# Arduino-UNO-Sheild.net
KiCad netlist of a schematic drawn in EAGLE
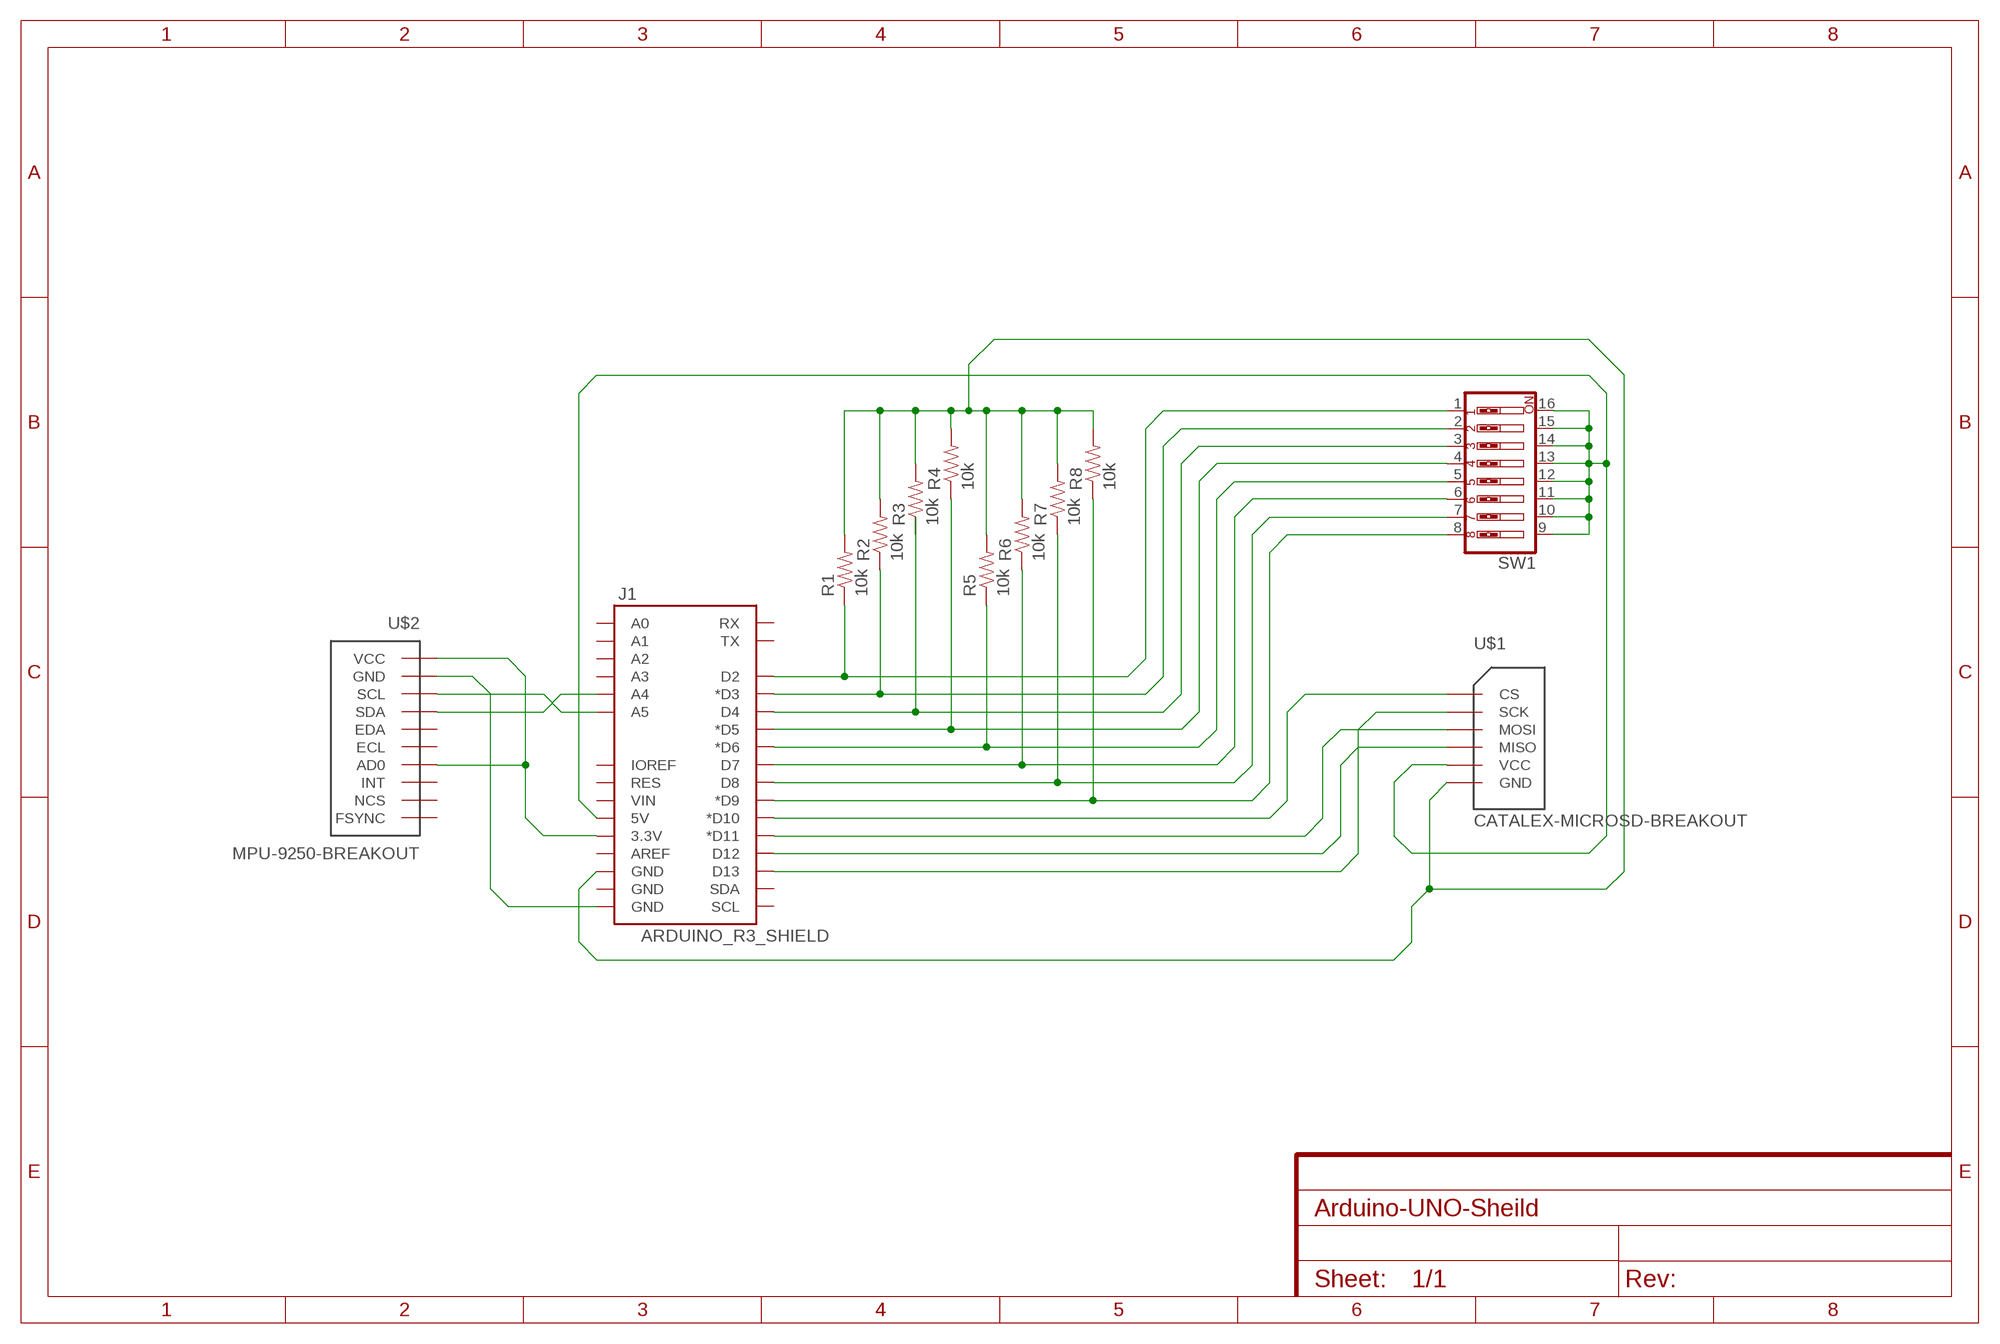
[diagram p0: schematic, sheet 1]

(export (version "E")
  (design (tool "Eeschema 10.0.6"))
  (components
    (comp (ref "J1")
      (value "ARDUINO_R3_SHIELD")
      (footprint "eagle-import:UNO_R3_SHIELD")
      (libsource (lib "eagle-import") (part "ARDUINO_R3_SHIELD"))
    )
    (comp (ref "R1")
      (value "10k")
      (footprint "eagle-import:AXIAL-0.3-KIT")
      (libsource (lib "eagle-import") (part "RESISTORKIT"))
    )
    (comp (ref "R2")
      (value "10k")
      (footprint "eagle-import:AXIAL-0.3-KIT")
      (libsource (lib "eagle-import") (part "RESISTORKIT"))
    )
    (comp (ref "R3")
      (value "10k")
      (footprint "eagle-import:AXIAL-0.3-KIT")
      (libsource (lib "eagle-import") (part "RESISTORKIT"))
    )
    (comp (ref "R4")
      (value "10k")
      (footprint "eagle-import:AXIAL-0.3-KIT")
      (libsource (lib "eagle-import") (part "RESISTORKIT"))
    )
    (comp (ref "R5")
      (value "10k")
      (footprint "eagle-import:AXIAL-0.3-KIT")
      (libsource (lib "eagle-import") (part "RESISTORKIT"))
    )
    (comp (ref "R6")
      (value "10k")
      (footprint "eagle-import:AXIAL-0.3-KIT")
      (libsource (lib "eagle-import") (part "RESISTORKIT"))
    )
    (comp (ref "R7")
      (value "10k")
      (footprint "eagle-import:AXIAL-0.3-KIT")
      (libsource (lib "eagle-import") (part "RESISTORKIT"))
    )
    (comp (ref "R8")
      (value "10k")
      (footprint "eagle-import:AXIAL-0.3-KIT")
      (libsource (lib "eagle-import") (part "RESISTORKIT"))
    )
    (comp (ref "SW1")
      (value "SW_DIP-8")
      (footprint "eagle-import:DIPSWITCH-08")
      (libsource (lib "eagle-import") (part "SW_DIP-8"))
    )
    (comp (ref "U$1")
      (value "CATALEX-MICROSD-BREAKOUT")
      (footprint "eagle-import:CATALEX-MICROSD-BREAKOUT")
      (libsource (lib "eagle-import") (part "CATALEX-MICROSD-BREAKOUT"))
    )
    (comp (ref "U$2")
      (value "MPU-9250-BREAKOUT")
      (footprint "eagle-import:MPU-9250-BREAKOUT")
      (libsource (lib "eagle-import") (part "MPU-9250-BREAKOUT"))
    )
  )
  (nets
    (net (code "1") (name "Net-(J1-*D3)") (class "Default")
      (node (ref "J1") (pin "D3") (pinfunction "*D3_D3") (pintype "bidirectional"))
      (node (ref "R2") (pin "P$1") (pinfunction "1_P$1") (pintype "passive"))
      (node (ref "SW1") (pin "2") (pinfunction "2_2") (pintype "passive"))
    )
    (net (code "2") (name "Net-(J1-*D5)") (class "Default")
      (node (ref "J1") (pin "D5") (pinfunction "*D5_D5") (pintype "bidirectional"))
      (node (ref "R4") (pin "P$1") (pinfunction "1_P$1") (pintype "passive"))
      (node (ref "SW1") (pin "4") (pinfunction "4_4") (pintype "passive"))
    )
    (net (code "3") (name "Net-(J1-*D6)") (class "Default")
      (node (ref "J1") (pin "D6") (pinfunction "*D6_D6") (pintype "bidirectional"))
      (node (ref "R5") (pin "P$1") (pinfunction "1_P$1") (pintype "passive"))
      (node (ref "SW1") (pin "5") (pinfunction "5_5") (pintype "passive"))
    )
    (net (code "4") (name "Net-(J1-*D9)") (class "Default")
      (node (ref "J1") (pin "D9") (pinfunction "*D9_D9") (pintype "bidirectional"))
      (node (ref "R8") (pin "P$1") (pinfunction "1_P$1") (pintype "passive"))
      (node (ref "SW1") (pin "8") (pinfunction "8_8") (pintype "passive"))
    )
    (net (code "5") (name "Net-(J1-*D10)") (class "Default")
      (node (ref "J1") (pin "D10") (pinfunction "*D10_D10") (pintype "bidirectional"))
      (node (ref "U$1") (pin "CS") (pinfunction "CS_CS") (pintype "bidirectional"))
    )
    (net (code "6") (name "Net-(J1-*D11)") (class "Default")
      (node (ref "J1") (pin "D11") (pinfunction "*D11_D11") (pintype "bidirectional"))
      (node (ref "U$1") (pin "MOSI") (pinfunction "MOSI_MOSI") (pintype "bidirectional"))
    )
    (net (code "7") (name "Net-(J1-GND-PadGND@0)") (class "Default")
      (node (ref "J1") (pin "GND@0") (pinfunction "GND_GND@0") (pintype "bidirectional"))
      (node (ref "U$2") (pin "GND") (pinfunction "GND_GND") (pintype "bidirectional"))
    )
    (net (code "8") (name "Net-(J1-Pad3.3V)") (class "Default")
      (node (ref "J1") (pin "3.3V") (pinfunction "3.3V_3.3V") (pintype "bidirectional"))
      (node (ref "U$2") (pin "AD0") (pinfunction "AD0_AD0") (pintype "bidirectional"))
      (node (ref "U$2") (pin "VCC") (pinfunction "VCC_VCC") (pintype "bidirectional"))
    )
    (net (code "9") (name "Net-(J1-Pad5V)") (class "Default")
      (node (ref "J1") (pin "5V") (pinfunction "5V_5V") (pintype "bidirectional"))
      (node (ref "SW1") (pin "10") (pinfunction "10_10") (pintype "passive"))
      (node (ref "SW1") (pin "11") (pinfunction "11_11") (pintype "passive"))
      (node (ref "SW1") (pin "12") (pinfunction "12_12") (pintype "passive"))
      (node (ref "SW1") (pin "13") (pinfunction "13_13") (pintype "passive"))
      (node (ref "SW1") (pin "14") (pinfunction "14_14") (pintype "passive"))
      (node (ref "SW1") (pin "15") (pinfunction "15_15") (pintype "passive"))
      (node (ref "SW1") (pin "16") (pinfunction "16_16") (pintype "passive"))
      (node (ref "SW1") (pin "9") (pinfunction "9_9") (pintype "passive"))
      (node (ref "U$1") (pin "VCC") (pinfunction "VCC_VCC") (pintype "bidirectional"))
    )
    (net (code "10") (name "Net-(J1-PadA4)") (class "Default")
      (node (ref "J1") (pin "A4") (pinfunction "A4_A4") (pintype "bidirectional"))
      (node (ref "U$2") (pin "SDA") (pinfunction "SDA_SDA") (pintype "bidirectional"))
    )
    (net (code "11") (name "Net-(J1-PadA5)") (class "Default")
      (node (ref "J1") (pin "A5") (pinfunction "A5_A5") (pintype "bidirectional"))
      (node (ref "U$2") (pin "SCL") (pinfunction "SCL_SCL") (pintype "bidirectional"))
    )
    (net (code "12") (name "Net-(J1-PadD4)") (class "Default")
      (node (ref "J1") (pin "D4") (pinfunction "D4_D4") (pintype "bidirectional"))
      (node (ref "SW1") (pin "3") (pinfunction "3_3") (pintype "passive"))
    )
    (net (code "13") (name "Net-(J1-PadD12)") (class "Default")
      (node (ref "J1") (pin "D12") (pinfunction "D12_D12") (pintype "bidirectional"))
      (node (ref "U$1") (pin "MISO") (pinfunction "MISO_MISO") (pintype "bidirectional"))
    )
    (net (code "14") (name "Net-(J1-PadD13)") (class "Default")
      (node (ref "J1") (pin "D13") (pinfunction "D13_D13") (pintype "bidirectional"))
      (node (ref "U$1") (pin "SCK") (pinfunction "SCK_SCK") (pintype "bidirectional"))
    )
    (net (code "15") (name "Net-(R1-1)") (class "Default")
      (node (ref "J1") (pin "D2") (pinfunction "D2_D2") (pintype "bidirectional"))
      (node (ref "R1") (pin "P$1") (pinfunction "1_P$1") (pintype "passive"))
      (node (ref "SW1") (pin "1") (pinfunction "1_1") (pintype "passive"))
    )
    (net (code "16") (name "Net-(R1-2)") (class "Default")
      (node (ref "J1") (pin "GND@2") (pinfunction "GND_GND@2") (pintype "bidirectional"))
      (node (ref "R1") (pin "P$2") (pinfunction "2_P$2") (pintype "passive"))
      (node (ref "R2") (pin "P$2") (pinfunction "2_P$2") (pintype "passive"))
      (node (ref "R3") (pin "P$2") (pinfunction "2_P$2") (pintype "passive"))
      (node (ref "R4") (pin "P$2") (pinfunction "2_P$2") (pintype "passive"))
      (node (ref "R5") (pin "P$2") (pinfunction "2_P$2") (pintype "passive"))
      (node (ref "R6") (pin "P$2") (pinfunction "2_P$2") (pintype "passive"))
      (node (ref "R7") (pin "P$2") (pinfunction "2_P$2") (pintype "passive"))
      (node (ref "R8") (pin "P$2") (pinfunction "2_P$2") (pintype "passive"))
      (node (ref "U$1") (pin "GND") (pinfunction "GND_GND") (pintype "bidirectional"))
    )
    (net (code "17") (name "Net-(R6-1)") (class "Default")
      (node (ref "J1") (pin "D7") (pinfunction "D7_D7") (pintype "bidirectional"))
      (node (ref "R6") (pin "P$1") (pinfunction "1_P$1") (pintype "passive"))
      (node (ref "SW1") (pin "6") (pinfunction "6_6") (pintype "passive"))
    )
    (net (code "18") (name "Net-(R7-1)") (class "Default")
      (node (ref "J1") (pin "D8") (pinfunction "D8_D8") (pintype "bidirectional"))
      (node (ref "R7") (pin "P$1") (pinfunction "1_P$1") (pintype "passive"))
      (node (ref "SW1") (pin "7") (pinfunction "7_7") (pintype "passive"))
    )
    (net (code "19") (name "unconnected-(J1-GND-PadGND@1)") (class "Default")
      (node (ref "J1") (pin "GND@1") (pinfunction "GND_GND@1") (pintype "bidirectional"))
    )
    (net (code "20") (name "unconnected-(J1-PadA0)") (class "Default")
      (node (ref "J1") (pin "A0") (pinfunction "A0_A0") (pintype "bidirectional"))
    )
    (net (code "21") (name "unconnected-(J1-PadA1)") (class "Default")
      (node (ref "J1") (pin "A1") (pinfunction "A1_A1") (pintype "bidirectional"))
    )
    (net (code "22") (name "unconnected-(J1-PadA2)") (class "Default")
      (node (ref "J1") (pin "A2") (pinfunction "A2_A2") (pintype "bidirectional"))
    )
    (net (code "23") (name "unconnected-(J1-PadA3)") (class "Default")
      (node (ref "J1") (pin "A3") (pinfunction "A3_A3") (pintype "bidirectional"))
    )
    (net (code "24") (name "unconnected-(J1-PadAREF)") (class "Default")
      (node (ref "J1") (pin "AREF") (pinfunction "AREF_AREF") (pintype "bidirectional"))
    )
    (net (code "25") (name "unconnected-(J1-PadIOREF)") (class "Default")
      (node (ref "J1") (pin "IOREF") (pinfunction "IOREF_IOREF") (pintype "bidirectional"))
    )
    (net (code "26") (name "unconnected-(J1-PadRES)") (class "Default")
      (node (ref "J1") (pin "RES") (pinfunction "RES_RES") (pintype "bidirectional"))
    )
    (net (code "27") (name "unconnected-(J1-PadRX)") (class "Default")
      (node (ref "J1") (pin "RX") (pinfunction "RX_RX") (pintype "bidirectional"))
    )
    (net (code "28") (name "unconnected-(J1-PadSCL)") (class "Default")
      (node (ref "J1") (pin "SCL") (pinfunction "SCL_SCL") (pintype "bidirectional"))
    )
    (net (code "29") (name "unconnected-(J1-PadSDA)") (class "Default")
      (node (ref "J1") (pin "SDA") (pinfunction "SDA_SDA") (pintype "bidirectional"))
    )
    (net (code "30") (name "unconnected-(J1-PadTX)") (class "Default")
      (node (ref "J1") (pin "TX") (pinfunction "TX_TX") (pintype "bidirectional"))
    )
    (net (code "31") (name "unconnected-(J1-PadVIN)") (class "Default")
      (node (ref "J1") (pin "VIN") (pinfunction "VIN_VIN") (pintype "bidirectional"))
    )
    (net (code "32") (name "unconnected-(R3-1-PadP$1)") (class "Default")
      (node (ref "R3") (pin "P$1") (pinfunction "1_P$1") (pintype "passive"))
    )
    (net (code "33") (name "unconnected-(U$2-PadECL)") (class "Default")
      (node (ref "U$2") (pin "ECL") (pinfunction "ECL_ECL") (pintype "bidirectional"))
    )
    (net (code "34") (name "unconnected-(U$2-PadEDA)") (class "Default")
      (node (ref "U$2") (pin "EDA") (pinfunction "EDA_EDA") (pintype "bidirectional"))
    )
    (net (code "35") (name "unconnected-(U$2-PadFSYNC)") (class "Default")
      (node (ref "U$2") (pin "FSYNC") (pinfunction "FSYNC_FSYNC") (pintype "bidirectional"))
    )
    (net (code "36") (name "unconnected-(U$2-PadINT)") (class "Default")
      (node (ref "U$2") (pin "INT") (pinfunction "INT_INT") (pintype "bidirectional"))
    )
    (net (code "37") (name "unconnected-(U$2-PadNCS)") (class "Default")
      (node (ref "U$2") (pin "NCS") (pinfunction "NCS_NCS") (pintype "bidirectional"))
    )
  )
)
